# MCU.net
KiCad netlist of a schematic drawn in Altium Designer
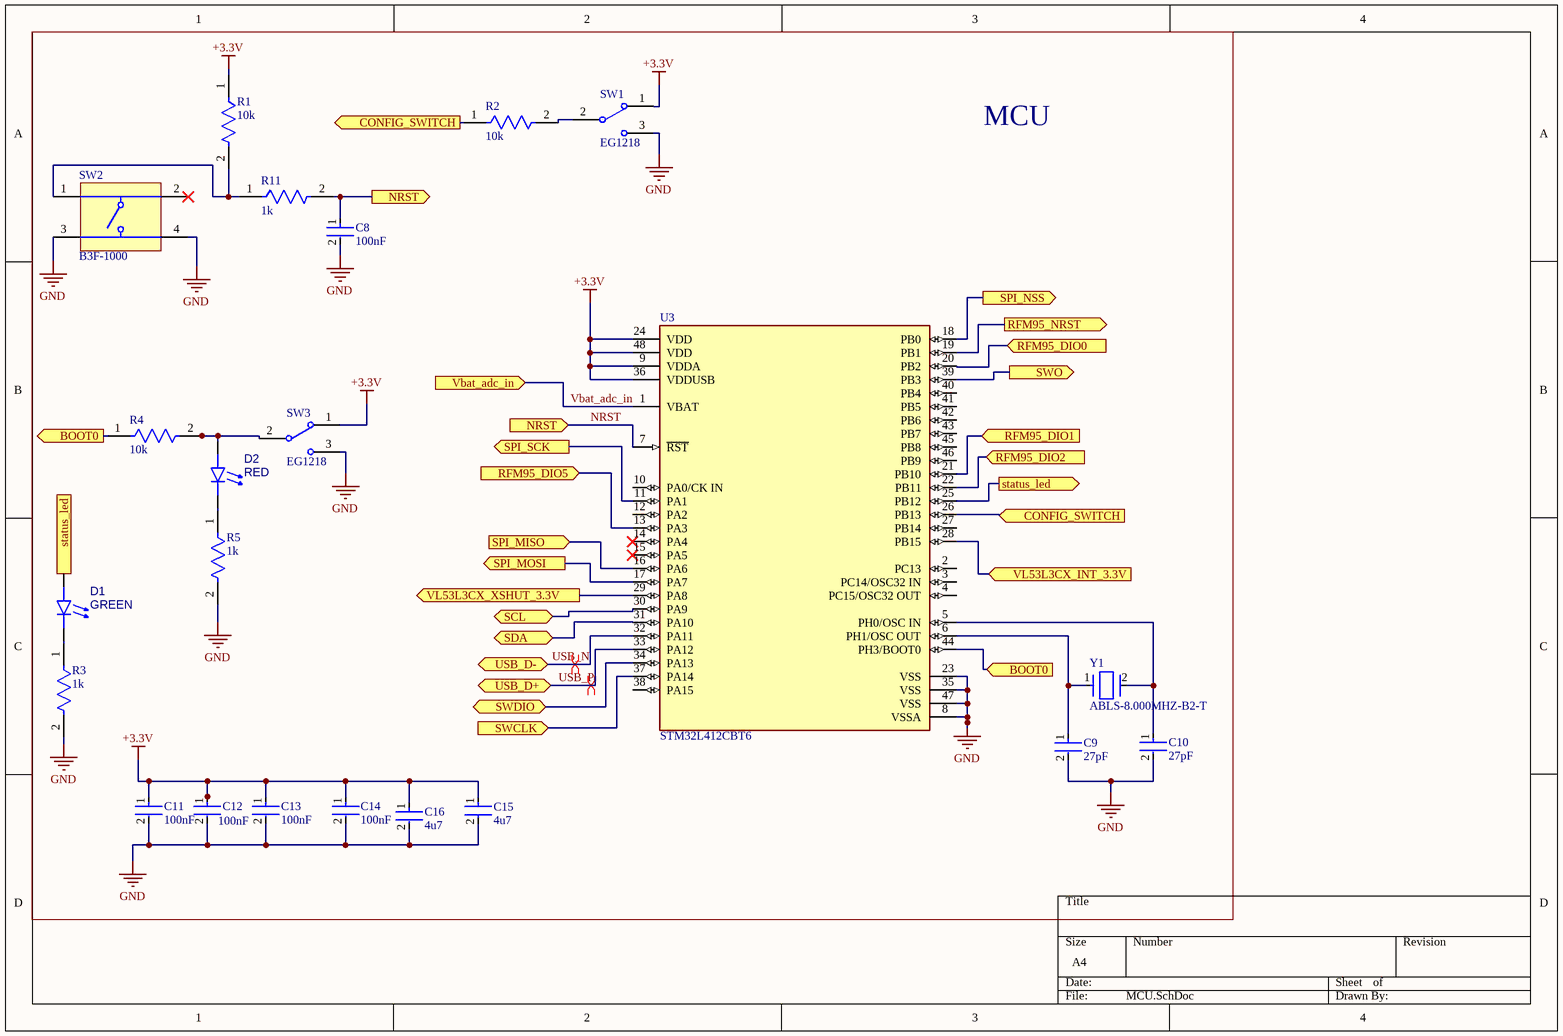
[diagram p0: MCU.SchDoc]

(export (version "E")
  (design (tool "Eeschema 10.0.6"))
  (components
    (comp (ref "C8")
      (value "100nF")
      (footprint "FP-C1206C-EB-MFG")
      (description "CAP CER 0.1UF 16V 10% X7R 1206")
      (fields (field (name "MANUFACTURER PART NUMBER") "C1206C104K4RACTU") (field (name "TOLERANCE") "0.1"))
      (libsource (lib "Altium Content Vault") (part "b4654b650e69147ec39a6b967a45e02"))
    )
    (comp (ref "C9")
      (value "27pF")
      (footprint "FP-GCM31A-0_2-MFG")
      (description "Ceramic Capacitor for Automotive 27pF ±1% 1kVDC C0G 1206 Paper T/R")
      (libsource (lib "Altium Content Vault") (part "11868f565c42a9108669ba33697ecf6"))
    )
    (comp (ref "C10")
      (value "27pF")
      (footprint "FP-GCM31A-0_2-MFG")
      (description "Ceramic Capacitor for Automotive 27pF ±1% 1kVDC C0G 1206 Paper T/R")
      (libsource (lib "Altium Content Vault") (part "11868f565c42a9108669ba33697ecf6"))
    )
    (comp (ref "C11")
      (value "100nF")
      (footprint "FP-C1206C-EB-MFG")
      (description "CAP CER 0.1UF 16V 10% X7R 1206")
      (fields (field (name "MANUFACTURER PART NUMBER") "C1206C104K4RACTU") (field (name "TOLERANCE") "0.1"))
      (libsource (lib "Altium Content Vault") (part "b4654b650e69147ec39a6b967a45e02"))
    )
    (comp (ref "C12")
      (value "100nF")
      (footprint "FP-C1206C-EB-MFG")
      (description "CAP CER 0.1UF 16V 10% X7R 1206")
      (fields (field (name "MANUFACTURER PART NUMBER") "C1206C104K4RACTU") (field (name "TOLERANCE") "0.1"))
      (libsource (lib "Altium Content Vault") (part "b4654b650e69147ec39a6b967a45e02"))
    )
    (comp (ref "C13")
      (value "100nF")
      (footprint "FP-C1206C-EB-MFG")
      (description "CAP CER 0.1UF 16V 10% X7R 1206")
      (fields (field (name "MANUFACTURER PART NUMBER") "C1206C104K4RACTU") (field (name "TOLERANCE") "0.1"))
      (libsource (lib "Altium Content Vault") (part "b4654b650e69147ec39a6b967a45e02"))
    )
    (comp (ref "C14")
      (value "100nF")
      (footprint "FP-C1206C-EB-MFG")
      (description "CAP CER 0.1UF 16V 10% X7R 1206")
      (fields (field (name "MANUFACTURER PART NUMBER") "C1206C104K4RACTU") (field (name "TOLERANCE") "0.1"))
      (libsource (lib "Altium Content Vault") (part "b4654b650e69147ec39a6b967a45e02"))
    )
    (comp (ref "C15")
      (value "4u7")
      (footprint "FP-GRM21B-0_15-MFG")
      (description "Chip Multilayer Ceramic Capacitors for General Purpose, 0805, 4.7uF, X7R, 15%, 10%, 10V")
      (fields (field (name "TOLERANCE") "10%"))
      (libsource (lib "Altium Content Vault") (part "b4654b650e69147ec39a6b967a45e02"))
    )
    (comp (ref "C16")
      (value "4u7")
      (footprint "FP-GRM21B-0_15-MFG")
      (description "Chip Multilayer Ceramic Capacitors for General Purpose, 0805, 4.7uF, X7R, 15%, 10%, 10V")
      (fields (field (name "TOLERANCE") "10%"))
      (libsource (lib "Altium Content Vault") (part "b4654b650e69147ec39a6b967a45e02"))
    )
    (comp (ref "D1")
      (value "GREEN")
      (footprint "156120VS75000-Footprint-1")
      (description "Single Color LED")
      (libsource (lib "tutorial_PCB") (part "DIODE-LED-2"))
    )
    (comp (ref "D2")
      (value "RED")
      (footprint "156120RS75000-Footprint-1")
      (description "Single Color LED")
      (libsource (lib "tutorial_PCB") (part "DIODE-LED-2"))
    )
    (comp (ref "R1")
      (value "10k")
      (footprint "FP-RMCF1206-IPC_C")
      (description "10kΩ ±5% 0.25W 1206 Thick Film Chip Resistor AEC-Q200 compliant")
      (fields (field (name "TOLERANCE") "5%"))
      (libsource (lib "Altium Content Vault") (part "1029c3af85768c4190bb7ad29bc67b5"))
    )
    (comp (ref "R2")
      (value "10k")
      (footprint "FP-RMCF1206-IPC_C")
      (description "10kΩ ±5% 0.25W 1206 Thick Film Chip Resistor AEC-Q200 compliant")
      (fields (field (name "TOLERANCE") "5%"))
      (libsource (lib "Altium Content Vault") (part "1029c3af85768c4190bb7ad29bc67b5"))
    )
    (comp (ref "R3")
      (value "1k")
      (footprint "FP-RMCF1206-MFG")
      (description "1kΩ ±5% 0.25W 1206 Thick Film Chip Resistor AEC-Q200 compliant")
      (fields (field (name "TOLERANCE") "5%"))
      (libsource (lib "Altium Content Vault") (part "1029c3af85768c4190bb7ad29bc67b5"))
    )
    (comp (ref "R4")
      (value "10k")
      (footprint "FP-RMCF1206-IPC_C")
      (description "10kΩ ±5% 0.25W 1206 Thick Film Chip Resistor AEC-Q200 compliant")
      (fields (field (name "TOLERANCE") "5%"))
      (libsource (lib "Altium Content Vault") (part "1029c3af85768c4190bb7ad29bc67b5"))
    )
    (comp (ref "R5")
      (value "1k")
      (footprint "FP-RMCF1206-MFG")
      (description "1kΩ ±5% 0.25W 1206 Thick Film Chip Resistor AEC-Q200 compliant")
      (fields (field (name "TOLERANCE") "5%"))
      (libsource (lib "Altium Content Vault") (part "1029c3af85768c4190bb7ad29bc67b5"))
    )
    (comp (ref "R11")
      (value "1k")
      (footprint "FP-RMCF1206-MFG")
      (description "1kΩ ±5% 0.25W 1206 Thick Film Chip Resistor AEC-Q200 compliant")
      (fields (field (name "TOLERANCE") "5%"))
      (libsource (lib "Altium Content Vault") (part "1029c3af85768c4190bb7ad29bc67b5"))
    )
    (comp (ref "SW1")
      (value "EG1218")
      (footprint "ESWI-EG1218_V")
      (description "Slide Switch, SPDT, 500 V, -20 to 70 degC, 3-Pin THD, RoHS, Bulk")
      (fields (field (name "MANUFACTURER") "E-Switch"))
      (libsource (lib "tutorial_PCB") (part "SW-SPDT-3_B"))
    )
    (comp (ref "SW2")
      (value "B3F-1000")
      (footprint "OMRON-B3F-1000-4_V")
      (description "Tactile Switch, SPST-NO, 0.05 A, 24 V, -25 to 70 degC, 4-Pin THD, RoHS, Bulk")
      (fields (field (name "MANUFACTURER") "Omron Electronic Components"))
      (libsource (lib "tutorial_PCB") (part "SW-SPST-4_A"))
    )
    (comp (ref "SW3")
      (value "EG1218")
      (footprint "ESWI-EG1218_V")
      (description "Slide Switch, SPDT, 500 V, -20 to 70 degC, 3-Pin THD, RoHS, Bulk")
      (fields (field (name "MANUFACTURER") "E-Switch"))
      (libsource (lib "tutorial_PCB") (part "SW-SPDT-3_B"))
    )
    (comp (ref "U3")
      (value "STM32L412CBT6")
      (footprint "FP-LQFP48-5B-IPC_A")
      (description "IC MCU 32BIT 128KB FLASH 48LQFP")
      (libsource (lib "Altium Content Vault") (part "4ca86e70463fb043fbe0a04138c23db"))
    )
    (comp (ref "Y1")
      (value "ABLS-8.000MHZ-B2-T")
      (footprint "FP-ABLS-MFG")
      (description "CRYSTAL 8.0000MHZ 18PF SMD")
      (fields (field (name "TOLERANCE") "20ppm"))
      (libsource (lib "Altium Content Vault") (part "c23a69dc6c9e2f18f2079038eb95dd1"))
    )
  )
  (nets
    (net (code "1") (name "+3.3V") (class "Default")
      (node (ref "C11") (pin "1") (pinfunction "1_1") (pintype "passive"))
      (node (ref "C12") (pin "1") (pinfunction "1_1") (pintype "passive"))
      (node (ref "C13") (pin "1") (pinfunction "1_1") (pintype "passive"))
      (node (ref "C14") (pin "1") (pinfunction "1_1") (pintype "passive"))
      (node (ref "C15") (pin "1") (pinfunction "1_1") (pintype "passive"))
      (node (ref "C16") (pin "1") (pinfunction "1_1") (pintype "passive"))
      (node (ref "R1") (pin "1") (pinfunction "1_1") (pintype "passive"))
      (node (ref "SW1") (pin "1") (pinfunction "1_1") (pintype "passive"))
      (node (ref "SW3") (pin "1") (pinfunction "1_1") (pintype "passive"))
      (node (ref "U3") (pin "24") (pinfunction "VDD_24") (pintype "power_in"))
      (node (ref "U3") (pin "36") (pinfunction "VDDUSB_36") (pintype "power_in"))
      (node (ref "U3") (pin "48") (pinfunction "VDD_48") (pintype "power_in"))
      (node (ref "U3") (pin "9") (pinfunction "VDDA_9") (pintype "power_in"))
    )
    (net (code "2") (name "/BOOT0") (class "Default")
      (node (ref "R4") (pin "1") (pinfunction "1_1") (pintype "passive"))
      (node (ref "U3") (pin "44") (pinfunction "PH3/BOOT0_44") (pintype "bidirectional"))
    )
    (net (code "3") (name "/CONFIG_SWITCH") (class "Default")
      (node (ref "R2") (pin "1") (pinfunction "1_1") (pintype "passive"))
      (node (ref "U3") (pin "26") (pinfunction "PB13_26") (pintype "bidirectional"))
    )
    (net (code "4") (name "/NRST") (class "Default")
      (node (ref "C8") (pin "1") (pinfunction "1_1") (pintype "passive"))
      (node (ref "R11") (pin "2") (pinfunction "2_2") (pintype "passive"))
      (node (ref "U3") (pin "7") (pinfunction "~{RST}_7") (pintype "input"))
    )
    (net (code "5") (name "/RFM95_DIO0") (class "Default")
      (node (ref "U3") (pin "20") (pinfunction "PB2_20") (pintype "bidirectional"))
    )
    (net (code "6") (name "/RFM95_DIO1") (class "Default")
      (node (ref "U3") (pin "21") (pinfunction "PB10_21") (pintype "bidirectional"))
    )
    (net (code "7") (name "/RFM95_DIO2") (class "Default")
      (node (ref "U3") (pin "22") (pinfunction "PB11_22") (pintype "bidirectional"))
    )
    (net (code "8") (name "/RFM95_DIO5") (class "Default")
      (node (ref "U3") (pin "13") (pinfunction "PA3_13") (pintype "bidirectional"))
    )
    (net (code "9") (name "/RFM95_NRST") (class "Default")
      (node (ref "U3") (pin "19") (pinfunction "PB1_19") (pintype "bidirectional"))
    )
    (net (code "10") (name "/SCL") (class "Default")
      (node (ref "U3") (pin "30") (pinfunction "PA9_30") (pintype "bidirectional"))
    )
    (net (code "11") (name "/SDA") (class "Default")
      (node (ref "U3") (pin "31") (pinfunction "PA10_31") (pintype "bidirectional"))
    )
    (net (code "12") (name "/SPI_MISO") (class "Default")
      (node (ref "U3") (pin "16") (pinfunction "PA6_16") (pintype "bidirectional"))
    )
    (net (code "13") (name "/SPI_MOSI") (class "Default")
      (node (ref "U3") (pin "17") (pinfunction "PA7_17") (pintype "bidirectional"))
    )
    (net (code "14") (name "/SPI_NSS") (class "Default")
      (node (ref "U3") (pin "18") (pinfunction "PB0_18") (pintype "bidirectional"))
    )
    (net (code "15") (name "/SPI_SCK") (class "Default")
      (node (ref "U3") (pin "11") (pinfunction "PA1_11") (pintype "bidirectional"))
    )
    (net (code "16") (name "/SWCLK") (class "Default")
      (node (ref "U3") (pin "37") (pinfunction "PA14_37") (pintype "bidirectional"))
    )
    (net (code "17") (name "/SWDIO") (class "Default")
      (node (ref "U3") (pin "34") (pinfunction "PA13_34") (pintype "bidirectional"))
    )
    (net (code "18") (name "/SWO") (class "Default")
      (node (ref "U3") (pin "39") (pinfunction "PB3_39") (pintype "bidirectional"))
    )
    (net (code "19") (name "/USB_N") (class "Default")
      (node (ref "U3") (pin "32") (pinfunction "PA11_32") (pintype "bidirectional"))
    )
    (net (code "20") (name "/USB_P") (class "Default")
      (node (ref "U3") (pin "33") (pinfunction "PA12_33") (pintype "bidirectional"))
    )
    (net (code "21") (name "/VL53L3CX_INT_3.3V") (class "Default")
      (node (ref "U3") (pin "28") (pinfunction "PB15_28") (pintype "bidirectional"))
    )
    (net (code "22") (name "/VL53L3CX_XSHUT_3.3V") (class "Default")
      (node (ref "U3") (pin "29") (pinfunction "PA8_29") (pintype "bidirectional"))
    )
    (net (code "23") (name "/Vbat_adc_in") (class "Default")
      (node (ref "U3") (pin "1") (pinfunction "VBAT_1") (pintype "power_in"))
    )
    (net (code "24") (name "/status_led") (class "Default")
      (node (ref "D1") (pin "2") (pinfunction "A_2") (pintype "passive"))
      (node (ref "U3") (pin "25") (pinfunction "PB12_25") (pintype "bidirectional"))
    )
    (net (code "25") (name "GND") (class "Default")
      (node (ref "C10") (pin "2") (pinfunction "2_2") (pintype "passive"))
      (node (ref "C11") (pin "2") (pinfunction "2_2") (pintype "passive"))
      (node (ref "C12") (pin "2") (pinfunction "2_2") (pintype "passive"))
      (node (ref "C13") (pin "2") (pinfunction "2_2") (pintype "passive"))
      (node (ref "C14") (pin "2") (pinfunction "2_2") (pintype "passive"))
      (node (ref "C15") (pin "2") (pinfunction "2_2") (pintype "passive"))
      (node (ref "C16") (pin "2") (pinfunction "2_2") (pintype "passive"))
      (node (ref "C8") (pin "2") (pinfunction "2_2") (pintype "passive"))
      (node (ref "C9") (pin "2") (pinfunction "2_2") (pintype "passive"))
      (node (ref "R3") (pin "2") (pinfunction "2_2") (pintype "passive"))
      (node (ref "R5") (pin "2") (pinfunction "2_2") (pintype "passive"))
      (node (ref "SW1") (pin "3") (pinfunction "3_3") (pintype "passive"))
      (node (ref "SW2") (pin "3") (pinfunction "3_3") (pintype "passive"))
      (node (ref "SW2") (pin "4") (pinfunction "4_4") (pintype "passive"))
      (node (ref "SW3") (pin "3") (pinfunction "3_3") (pintype "passive"))
      (node (ref "U3") (pin "23") (pinfunction "VSS_23") (pintype "power_in"))
      (node (ref "U3") (pin "35") (pinfunction "VSS_35") (pintype "power_in"))
      (node (ref "U3") (pin "47") (pinfunction "VSS_47") (pintype "power_in"))
      (node (ref "U3") (pin "8") (pinfunction "VSSA_8") (pintype "power_in"))
    )
    (net (code "26") (name "Net-(D1-K)") (class "Default")
      (node (ref "D1") (pin "1") (pinfunction "K_1") (pintype "passive"))
      (node (ref "R3") (pin "1") (pinfunction "1_1") (pintype "passive"))
    )
    (net (code "27") (name "Net-(D2-A)") (class "Default")
      (node (ref "D2") (pin "2") (pinfunction "A_2") (pintype "passive"))
      (node (ref "R4") (pin "2") (pinfunction "2_2") (pintype "passive"))
      (node (ref "SW3") (pin "2") (pinfunction "COM_2") (pintype "passive"))
    )
    (net (code "28") (name "Net-(D2-K)") (class "Default")
      (node (ref "D2") (pin "1") (pinfunction "K_1") (pintype "passive"))
      (node (ref "R5") (pin "1") (pinfunction "1_1") (pintype "passive"))
    )
    (net (code "29") (name "Net-(R1-Pad2)") (class "Default")
      (node (ref "R1") (pin "2") (pinfunction "2_2") (pintype "passive"))
      (node (ref "R11") (pin "1") (pinfunction "1_1") (pintype "passive"))
      (node (ref "SW2") (pin "1") (pinfunction "1_1") (pintype "passive"))
    )
    (net (code "30") (name "Net-(SW1-COM)") (class "Default")
      (node (ref "R2") (pin "2") (pinfunction "2_2") (pintype "passive"))
      (node (ref "SW1") (pin "2") (pinfunction "COM_2") (pintype "passive"))
    )
    (net (code "31") (name "Net-(U3-PH0{slash}OSC_IN)") (class "Default")
      (node (ref "C10") (pin "1") (pinfunction "1_1") (pintype "passive"))
      (node (ref "U3") (pin "5") (pinfunction "PH0/OSC_IN_5") (pintype "bidirectional"))
      (node (ref "Y1") (pin "2") (pinfunction "2_2") (pintype "passive"))
    )
    (net (code "32") (name "Net-(U3-PH1{slash}OSC_OUT)") (class "Default")
      (node (ref "C9") (pin "1") (pinfunction "1_1") (pintype "passive"))
      (node (ref "U3") (pin "6") (pinfunction "PH1/OSC_OUT_6") (pintype "bidirectional"))
      (node (ref "Y1") (pin "1") (pinfunction "1_1") (pintype "passive"))
    )
    (net (code "33") (name "unconnected-(SW2-Pad2)") (class "Default")
      (node (ref "SW2") (pin "2") (pinfunction "2_2") (pintype "passive+no_connect"))
    )
    (net (code "34") (name "unconnected-(U3-PA0{slash}CK_IN-Pad10)") (class "Default")
      (node (ref "U3") (pin "10") (pinfunction "PA0/CK_IN_10") (pintype "bidirectional"))
    )
    (net (code "35") (name "unconnected-(U3-PA2-Pad12)") (class "Default")
      (node (ref "U3") (pin "12") (pinfunction "PA2_12") (pintype "bidirectional"))
    )
    (net (code "36") (name "unconnected-(U3-PA4-Pad14)") (class "Default")
      (node (ref "U3") (pin "14") (pinfunction "PA4_14") (pintype "bidirectional+no_connect"))
    )
    (net (code "37") (name "unconnected-(U3-PA5-Pad15)") (class "Default")
      (node (ref "U3") (pin "15") (pinfunction "PA5_15") (pintype "bidirectional+no_connect"))
    )
    (net (code "38") (name "unconnected-(U3-PA15-Pad38)") (class "Default")
      (node (ref "U3") (pin "38") (pinfunction "PA15_38") (pintype "bidirectional"))
    )
    (net (code "39") (name "unconnected-(U3-PB4-Pad40)") (class "Default")
      (node (ref "U3") (pin "40") (pinfunction "PB4_40") (pintype "bidirectional"))
    )
    (net (code "40") (name "unconnected-(U3-PB5-Pad41)") (class "Default")
      (node (ref "U3") (pin "41") (pinfunction "PB5_41") (pintype "bidirectional"))
    )
    (net (code "41") (name "unconnected-(U3-PB6-Pad42)") (class "Default")
      (node (ref "U3") (pin "42") (pinfunction "PB6_42") (pintype "bidirectional"))
    )
    (net (code "42") (name "unconnected-(U3-PB7-Pad43)") (class "Default")
      (node (ref "U3") (pin "43") (pinfunction "PB7_43") (pintype "bidirectional"))
    )
    (net (code "43") (name "unconnected-(U3-PB8-Pad45)") (class "Default")
      (node (ref "U3") (pin "45") (pinfunction "PB8_45") (pintype "bidirectional"))
    )
    (net (code "44") (name "unconnected-(U3-PB9-Pad46)") (class "Default")
      (node (ref "U3") (pin "46") (pinfunction "PB9_46") (pintype "bidirectional"))
    )
    (net (code "45") (name "unconnected-(U3-PB14-Pad27)") (class "Default")
      (node (ref "U3") (pin "27") (pinfunction "PB14_27") (pintype "bidirectional"))
    )
    (net (code "46") (name "unconnected-(U3-PC13-Pad2)") (class "Default")
      (node (ref "U3") (pin "2") (pinfunction "PC13_2") (pintype "bidirectional"))
    )
    (net (code "47") (name "unconnected-(U3-PC14{slash}OSC32_IN-Pad3)") (class "Default")
      (node (ref "U3") (pin "3") (pinfunction "PC14/OSC32_IN_3") (pintype "bidirectional"))
    )
    (net (code "48") (name "unconnected-(U3-PC15{slash}OSC32_OUT-Pad4)") (class "Default")
      (node (ref "U3") (pin "4") (pinfunction "PC15/OSC32_OUT_4") (pintype "bidirectional"))
    )
  )
)
